# smart-servo-addon-board_v52.net
KiCad netlist of a schematic drawn in EAGLE
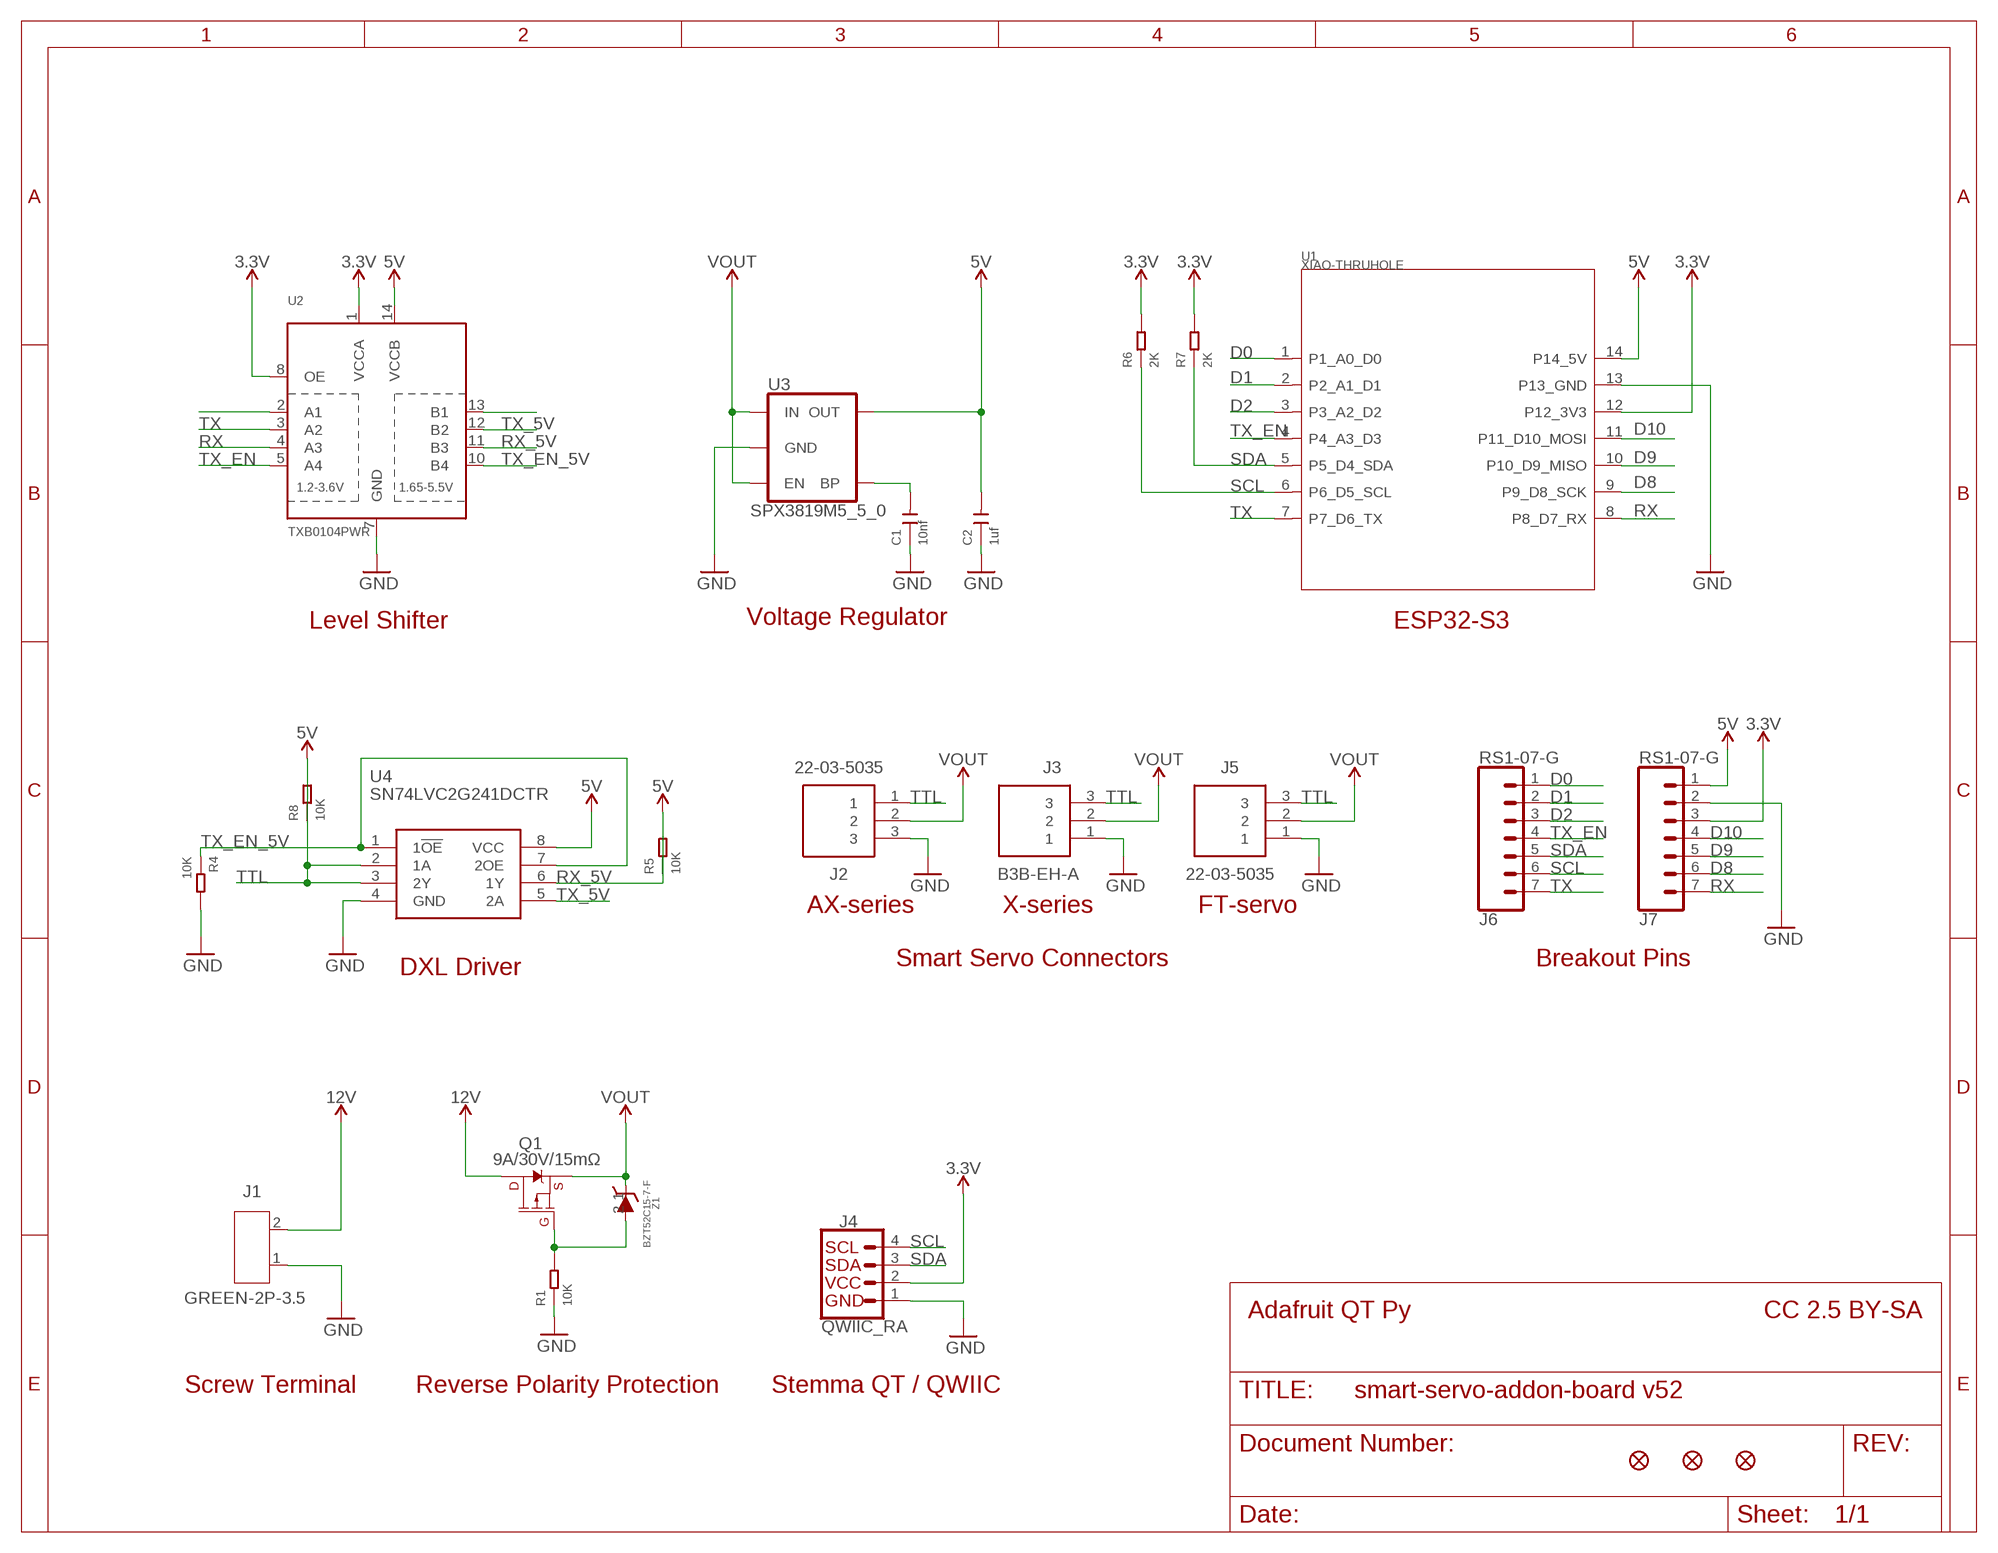
[diagram p0: schematic, sheet 1]

(export (version "E")
  (design (tool "Eeschema 10.0.6"))
  (components
    (comp (ref "C1")
      (value "10nf")
      (footprint "eagle-import:C0603")
      (fields (field (name "MPN") "CC0603KRX7R9BB103"))
      (libsource (lib "eagle-import") (part "CERAMIC-10NF-50V-10%-X7R(0603)"))
    )
    (comp (ref "C2")
      (value "1uf")
      (footprint "eagle-import:C0603")
      (fields (field (name "MPN") "CC0603KRX7R8BB105"))
      (libsource (lib "eagle-import") (part "CERAMIC-1UF-25V-10%-X7R(0603)"))
    )
    (comp (ref "FD4")
      (value "FIDUCIAL\"\"")
      (footprint "eagle-import:FIDUCIAL_1MM")
      (libsource (lib "eagle-import") (part "FIDUCIAL{dblquote}{dblquote}"))
    )
    (comp (ref "FD5")
      (value "FIDUCIAL\"\"")
      (footprint "eagle-import:FIDUCIAL_1MM")
      (libsource (lib "eagle-import") (part "FIDUCIAL{dblquote}{dblquote}"))
    )
    (comp (ref "FD6")
      (value "FIDUCIAL\"\"")
      (footprint "eagle-import:FIDUCIAL_1MM")
      (libsource (lib "eagle-import") (part "FIDUCIAL{dblquote}{dblquote}"))
    )
    (comp (ref "J1")
      (value "GREEN-2P-3.5")
      (footprint "eagle-import:H2-3.5-7.0X7.0MM")
      (libsource (lib "eagle-import") (part "SCREW-TERMINAL-GREEN(2P-3.5)"))
    )
    (comp (ref "J2")
      (value "22-03-5035")
      (footprint "eagle-import:SHDR3W60P0X250_1X3_990X490X590")
      (fields (field (name "MOUSER_PART_NUMBER") "538-22-03-5035"))
      (libsource (lib "eagle-import") (part "22-03-5035"))
    )
    (comp (ref "J3")
      (value "B3B-EH-A")
      (footprint "eagle-import:SHDR3W64P0X250_1X3_1000X380X60")
      (libsource (lib "eagle-import") (part "B3B-EH-A"))
    )
    (comp (ref "J4")
      (value "QWIIC_RA")
      (footprint "eagle-import:JST04_1MM_RA")
      (libsource (lib "eagle-import") (part "QWIIC_CONNECTORJS-1MM"))
    )
    (comp (ref "J5")
      (value "22-03-5035")
      (footprint "eagle-import:SHDR3W60P0X250_1X3_990X490X590")
      (fields (field (name "MOUSER_PART_NUMBER") "538-22-03-5035"))
      (libsource (lib "eagle-import") (part "22-03-5035"))
    )
    (comp (ref "J6")
      (value "RS1-07-G")
      (footprint "eagle-import:1X07")
      (libsource (lib "eagle-import") (part "CONN_07"))
    )
    (comp (ref "J7")
      (value "RS1-07-G")
      (footprint "eagle-import:1X07")
      (libsource (lib "eagle-import") (part "CONN_07"))
    )
    (comp (ref "Q1")
      (value "9A/30V/15mΩ")
      (footprint "eagle-import:8-POWERVDFN-3X3")
      (libsource (lib "eagle-import") (part "MOSFET_PCH-STL9P3LLH6"))
    )
    (comp (ref "R1")
      (value "10K")
      (footprint "eagle-import:R0603")
      (fields (field (name "MPN") "RC0603FR-0710KL"))
      (libsource (lib "eagle-import") (part "SMD-RES-10K-1%-1/10W(0603)"))
    )
    (comp (ref "R4")
      (value "10K")
      (footprint "eagle-import:R0603")
      (fields (field (name "MPN") "RC0603FR-0710KL"))
      (libsource (lib "eagle-import") (part "SMD-RES-10K-1%-1/10W(0603)"))
    )
    (comp (ref "R5")
      (value "10K")
      (footprint "eagle-import:R0603")
      (fields (field (name "MPN") "RC0603FR-0710KL"))
      (libsource (lib "eagle-import") (part "SMD-RES-10K-1%-1/10W(0603)"))
    )
    (comp (ref "R6")
      (value "2K")
      (footprint "eagle-import:R0603")
      (fields (field (name "MPN") "RC0603FR-0710KL"))
      (libsource (lib "eagle-import") (part "SMD-RES-10K-1%-1/10W(0603)"))
    )
    (comp (ref "R7")
      (value "2K")
      (footprint "eagle-import:R0603")
      (fields (field (name "MPN") "RC0603FR-0710KL"))
      (libsource (lib "eagle-import") (part "SMD-RES-10K-1%-1/10W(0603)"))
    )
    (comp (ref "R8")
      (value "10K")
      (footprint "eagle-import:R0603")
      (fields (field (name "MPN") "RC0603FR-0710KL"))
      (libsource (lib "eagle-import") (part "SMD-RES-10K-1%-1/10W(0603)"))
    )
    (comp (ref "U1")
      (value "XIAO-THRUHOLE")
      (footprint "eagle-import:XIAO-GENERIC-THRUHOLE-MODULE14P-2.54-21X17.8MM")
      (libsource (lib "eagle-import") (part "XIAO-THRUHOLE"))
    )
    (comp (ref "U2")
      (value "TXB0104PWR")
      (footprint "eagle-import:TSSOP14")
      (libsource (lib "eagle-import") (part "TXB0104PWR"))
    )
    (comp (ref "U3")
      (value "SPX3819M5_5_0")
      (footprint "eagle-import:SOT23-5")
      (libsource (lib "eagle-import") (part "V_REG_SPX3819-SOT23-5"))
    )
    (comp (ref "U4")
      (value "SN74LVC2G241DCTR")
      (footprint "eagle-import:SOP65P400X130-8N")
      (fields (field (name "MOUSER_PART_NUMBER") "595-SN74LVC2G241DCTR"))
      (libsource (lib "eagle-import") (part "SN74LVC2G241DCTR"))
    )
    (comp (ref "Z1")
      (value "BZT52C15-7-F")
      (footprint "eagle-import:SOD3716X145N")
      (fields (field (name "MOUSER_PART_NUMBER") "621-BZT52C15-F"))
      (libsource (lib "eagle-import") (part "BZT52C15-7-F"))
    )
  )
  (nets
    (net (code "1") (name "/D0") (class "Default")
      (node (ref "J6") (pin "1") (pinfunction "1_1") (pintype "passive"))
      (node (ref "U1") (pin "1") (pinfunction "P1_A0_D0_1") (pintype "bidirectional"))
    )
    (net (code "2") (name "/D1") (class "Default")
      (node (ref "J6") (pin "2") (pinfunction "2_2") (pintype "passive"))
      (node (ref "U1") (pin "2") (pinfunction "P2_A1_D1_2") (pintype "bidirectional"))
    )
    (net (code "3") (name "/D2") (class "Default")
      (node (ref "J6") (pin "3") (pinfunction "3_3") (pintype "passive"))
      (node (ref "U1") (pin "3") (pinfunction "P3_A2_D2_3") (pintype "bidirectional"))
    )
    (net (code "4") (name "/D8") (class "Default")
      (node (ref "J7") (pin "6") (pinfunction "6_6") (pintype "passive"))
      (node (ref "U1") (pin "9") (pinfunction "P9_D8_SCK_9") (pintype "bidirectional"))
    )
    (net (code "5") (name "/D9") (class "Default")
      (node (ref "J7") (pin "5") (pinfunction "5_5") (pintype "passive"))
      (node (ref "U1") (pin "10") (pinfunction "P10_D9_MISO_10") (pintype "bidirectional"))
    )
    (net (code "6") (name "/D10") (class "Default")
      (node (ref "J7") (pin "4") (pinfunction "4_4") (pintype "passive"))
      (node (ref "U1") (pin "11") (pinfunction "P11_D10_MOSI_11") (pintype "bidirectional"))
    )
    (net (code "7") (name "/RX") (class "Default")
      (node (ref "J7") (pin "7") (pinfunction "7_7") (pintype "passive"))
      (node (ref "U1") (pin "8") (pinfunction "P8_D7_RX_8") (pintype "bidirectional"))
      (node (ref "U2") (pin "4") (pinfunction "A3_4") (pintype "bidirectional"))
    )
    (net (code "8") (name "/RX_5V") (class "Default")
      (node (ref "R5") (pin "2") (pinfunction "2_2") (pintype "passive"))
      (node (ref "U2") (pin "11") (pinfunction "B3_11") (pintype "bidirectional"))
      (node (ref "U4") (pin "6") (pinfunction "1Y_6") (pintype "bidirectional"))
    )
    (net (code "9") (name "/SCL") (class "Default")
      (node (ref "J4") (pin "4") (pinfunction "4_4") (pintype "passive"))
      (node (ref "J6") (pin "6") (pinfunction "6_6") (pintype "passive"))
      (node (ref "R6") (pin "1") (pinfunction "1_1") (pintype "passive"))
      (node (ref "U1") (pin "6") (pinfunction "P6_D5_SCL_6") (pintype "bidirectional"))
    )
    (net (code "10") (name "/SDA") (class "Default")
      (node (ref "J4") (pin "3") (pinfunction "3_3") (pintype "passive"))
      (node (ref "J6") (pin "5") (pinfunction "5_5") (pintype "passive"))
      (node (ref "R7") (pin "1") (pinfunction "1_1") (pintype "passive"))
      (node (ref "U1") (pin "5") (pinfunction "P5_D4_SDA_5") (pintype "bidirectional"))
    )
    (net (code "11") (name "/TTL") (class "Default")
      (node (ref "J2") (pin "1") (pinfunction "1_1") (pintype "bidirectional"))
      (node (ref "J3") (pin "3") (pinfunction "3_3") (pintype "bidirectional"))
      (node (ref "J5") (pin "3") (pinfunction "3_3") (pintype "bidirectional"))
      (node (ref "R8") (pin "2") (pinfunction "2_2") (pintype "passive"))
      (node (ref "U4") (pin "2") (pinfunction "1A_2") (pintype "bidirectional"))
      (node (ref "U4") (pin "3") (pinfunction "2Y_3") (pintype "bidirectional"))
    )
    (net (code "12") (name "/TX") (class "Default")
      (node (ref "J6") (pin "7") (pinfunction "7_7") (pintype "passive"))
      (node (ref "U1") (pin "7") (pinfunction "P7_D6_TX_7") (pintype "bidirectional"))
      (node (ref "U2") (pin "3") (pinfunction "A2_3") (pintype "bidirectional"))
    )
    (net (code "13") (name "/TX_5V") (class "Default")
      (node (ref "U2") (pin "12") (pinfunction "B2_12") (pintype "bidirectional"))
      (node (ref "U4") (pin "5") (pinfunction "2A_5") (pintype "bidirectional"))
    )
    (net (code "14") (name "/TX_EN") (class "Default")
      (node (ref "J6") (pin "4") (pinfunction "4_4") (pintype "passive"))
      (node (ref "U1") (pin "4") (pinfunction "P4_A3_D3_4") (pintype "bidirectional"))
      (node (ref "U2") (pin "5") (pinfunction "A4_5") (pintype "bidirectional"))
    )
    (net (code "15") (name "/TX_EN_5V") (class "Default")
      (node (ref "R4") (pin "1") (pinfunction "1_1") (pintype "passive"))
      (node (ref "U2") (pin "10") (pinfunction "B4_10") (pintype "bidirectional"))
      (node (ref "U4") (pin "1") (pinfunction "1~{OE}_1") (pintype "bidirectional"))
      (node (ref "U4") (pin "7") (pinfunction "2OE_7") (pintype "bidirectional"))
    )
    (net (code "16") (name "3.3V") (class "Default")
      (node (ref "J4") (pin "2") (pinfunction "2_2") (pintype "power_in"))
      (node (ref "J7") (pin "3") (pinfunction "3_3") (pintype "passive"))
      (node (ref "R6") (pin "2") (pinfunction "2_2") (pintype "passive"))
      (node (ref "R7") (pin "2") (pinfunction "2_2") (pintype "passive"))
      (node (ref "U1") (pin "12") (pinfunction "P12_3V3_12") (pintype "bidirectional"))
      (node (ref "U2") (pin "1") (pinfunction "VCCA_1") (pintype "bidirectional"))
      (node (ref "U2") (pin "8") (pinfunction "OE_8") (pintype "bidirectional"))
    )
    (net (code "17") (name "5V") (class "Default")
      (node (ref "C2") (pin "2") (pinfunction "2_2") (pintype "passive"))
      (node (ref "J7") (pin "1") (pinfunction "1_1") (pintype "passive"))
      (node (ref "R5") (pin "1") (pinfunction "1_1") (pintype "passive"))
      (node (ref "R8") (pin "1") (pinfunction "1_1") (pintype "passive"))
      (node (ref "U1") (pin "14") (pinfunction "P14_5V_14") (pintype "bidirectional"))
      (node (ref "U2") (pin "14") (pinfunction "VCCB_14") (pintype "bidirectional"))
      (node (ref "U3") (pin "5") (pinfunction "OUT_5") (pintype "passive"))
      (node (ref "U4") (pin "8") (pinfunction "VCC_8") (pintype "bidirectional"))
    )
    (net (code "18") (name "12V") (class "Default")
      (node (ref "J1") (pin "2") (pinfunction "2_2") (pintype "bidirectional"))
      (node (ref "Q1") (pin "5@1") (pinfunction "D_5@1") (pintype "bidirectional"))
      (node (ref "Q1") (pin "5@2") (pinfunction "D_5@2") (pintype "bidirectional"))
      (node (ref "Q1") (pin "5@3") (pinfunction "D_5@3") (pintype "bidirectional"))
    )
    (net (code "19") (name "GND") (class "Default")
      (node (ref "C1") (pin "1") (pinfunction "1_1") (pintype "passive"))
      (node (ref "C2") (pin "1") (pinfunction "1_1") (pintype "passive"))
      (node (ref "J1") (pin "1") (pinfunction "1_1") (pintype "bidirectional"))
      (node (ref "J2") (pin "3") (pinfunction "3_3") (pintype "bidirectional"))
      (node (ref "J3") (pin "1") (pinfunction "1_1") (pintype "bidirectional"))
      (node (ref "J4") (pin "1") (pinfunction "1_1") (pintype "power_in"))
      (node (ref "J5") (pin "1") (pinfunction "1_1") (pintype "bidirectional"))
      (node (ref "J7") (pin "2") (pinfunction "2_2") (pintype "passive"))
      (node (ref "R1") (pin "1") (pinfunction "1_1") (pintype "passive"))
      (node (ref "R4") (pin "2") (pinfunction "2_2") (pintype "passive"))
      (node (ref "U1") (pin "13") (pinfunction "P13_GND_13") (pintype "bidirectional"))
      (node (ref "U2") (pin "7") (pinfunction "GND_7") (pintype "bidirectional"))
      (node (ref "U3") (pin "2") (pinfunction "GND_2") (pintype "input"))
      (node (ref "U4") (pin "4") (pinfunction "GND_4") (pintype "bidirectional"))
    )
    (net (code "20") (name "Net-(Q1-G)") (class "Default")
      (node (ref "Q1") (pin "4") (pinfunction "G_4") (pintype "bidirectional"))
      (node (ref "R1") (pin "2") (pinfunction "2_2") (pintype "passive"))
      (node (ref "Z1") (pin "2") (pinfunction "A_2") (pintype "bidirectional"))
    )
    (net (code "21") (name "Net-(U3-BP)") (class "Default")
      (node (ref "C1") (pin "2") (pinfunction "2_2") (pintype "passive"))
      (node (ref "U3") (pin "4") (pinfunction "BP_4") (pintype "input"))
    )
    (net (code "22") (name "VOUT") (class "Default")
      (node (ref "J2") (pin "2") (pinfunction "2_2") (pintype "bidirectional"))
      (node (ref "J3") (pin "2") (pinfunction "2_2") (pintype "bidirectional"))
      (node (ref "J5") (pin "2") (pinfunction "2_2") (pintype "bidirectional"))
      (node (ref "Q1") (pin "1") (pinfunction "S_1") (pintype "bidirectional"))
      (node (ref "Q1") (pin "2") (pinfunction "S_2") (pintype "bidirectional"))
      (node (ref "Q1") (pin "3") (pinfunction "S_3") (pintype "bidirectional"))
      (node (ref "U3") (pin "1") (pinfunction "IN_1") (pintype "input"))
      (node (ref "U3") (pin "3") (pinfunction "EN_3") (pintype "input"))
      (node (ref "Z1") (pin "1") (pinfunction "K_1") (pintype "bidirectional"))
    )
    (net (code "23") (name "unconnected-(U2-A1-Pad2)") (class "Default")
      (node (ref "U2") (pin "2") (pinfunction "A1_2") (pintype "bidirectional"))
    )
    (net (code "24") (name "unconnected-(U2-B1-Pad13)") (class "Default")
      (node (ref "U2") (pin "13") (pinfunction "B1_13") (pintype "bidirectional"))
    )
  )
)
